# AUDIO.net
KiCad netlist of a schematic drawn in Altium Designer
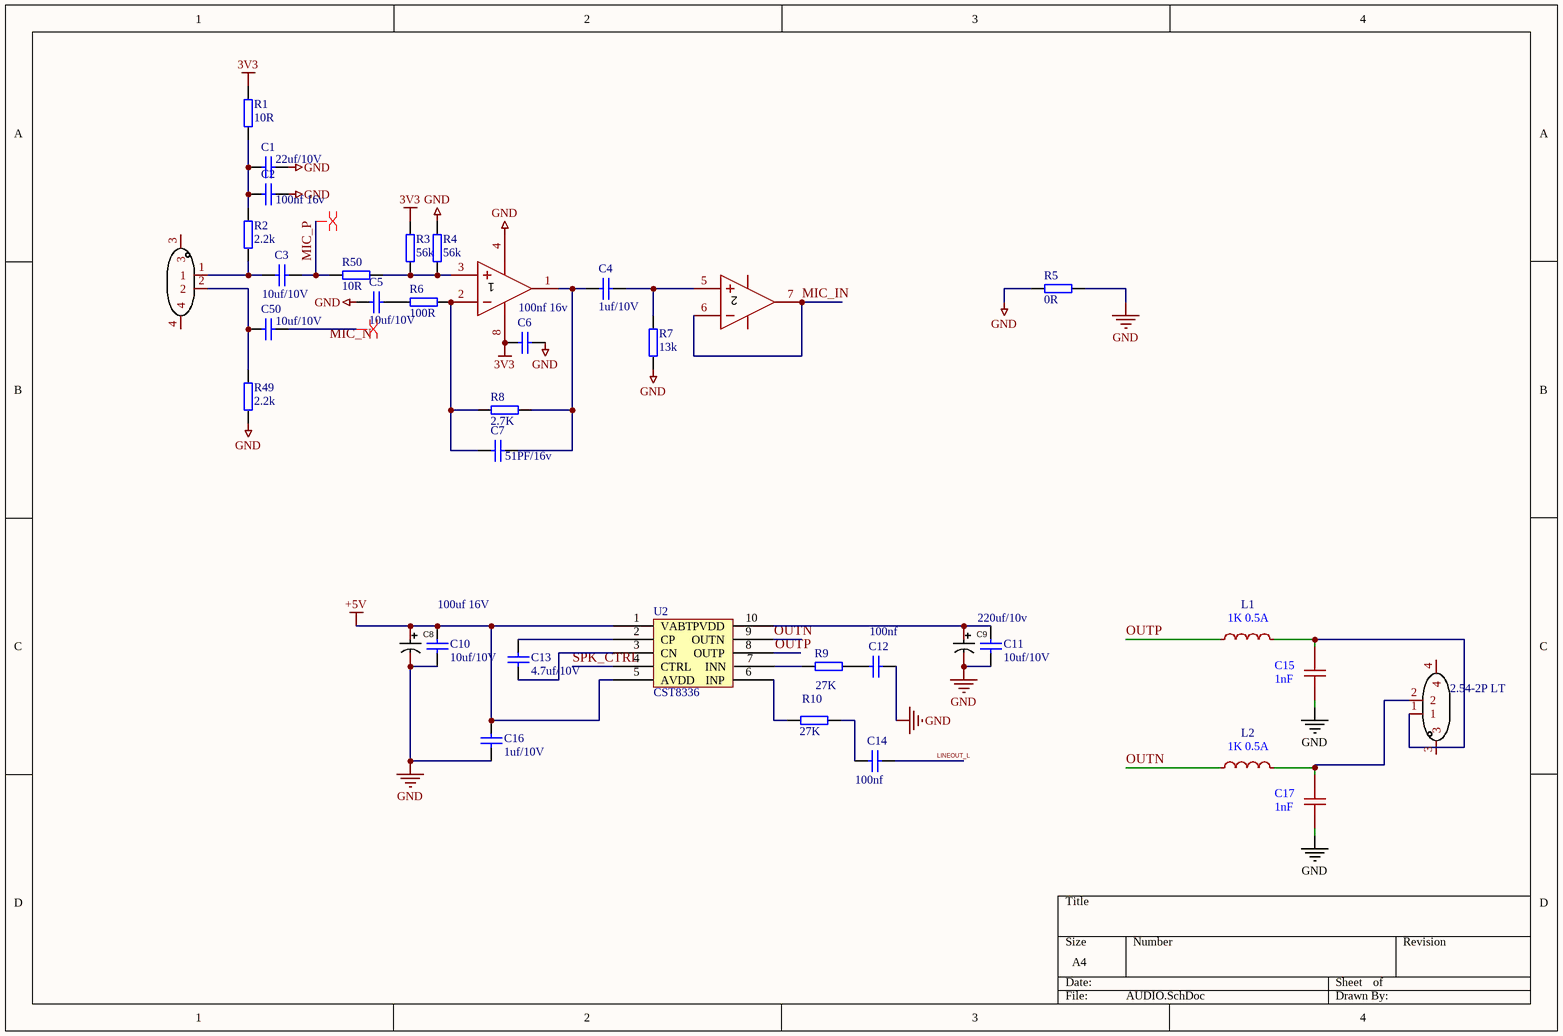
[diagram p0: AUDIO.SchDoc]

(export (version "E")
  (design (tool "Eeschema 10.0.6"))
  (components
    (comp (ref "C1")
      (value "22uf/10V")
      (footprint "0603_C")
      (description "Capacitor")
      (fields (field (name "PUBLISHER") "Altium Limited"))
      (libsource (lib "*") (part "Cap"))
    )
    (comp (ref "C2")
      (value "100nf 16v")
      (footprint "0603_C")
      (description "Capacitor")
      (fields (field (name "PUBLISHER") "Altium Limited"))
      (libsource (lib "*") (part "Cap"))
    )
    (comp (ref "C3")
      (value "10uf/10V")
      (footprint "0603_C")
      (description "Capacitor")
      (fields (field (name "PUBLISHER") "Altium Limited"))
      (libsource (lib "*") (part "Cap"))
    )
    (comp (ref "C4")
      (value "1uf/10V")
      (footprint "0603_C")
      (description "Capacitor")
      (fields (field (name "PUBLISHER") "Altium Limited"))
      (libsource (lib "*") (part "Cap"))
    )
    (comp (ref "C5")
      (value "10uf/10V")
      (footprint "0603_C")
      (description "Capacitor")
      (fields (field (name "PUBLISHER") "Altium Limited"))
      (libsource (lib "*") (part "Cap"))
    )
    (comp (ref "C6")
      (value "100nf 16v")
      (footprint "0603_C")
      (description "Capacitor")
      (fields (field (name "PUBLISHER") "Altium Limited"))
      (libsource (lib "*") (part "Cap"))
    )
    (comp (ref "C7")
      (value "51PF/16v")
      (footprint "0603_C")
      (description "Capacitor")
      (fields (field (name "PUBLISHER") "Altium Limited"))
      (libsource (lib "*") (part "Cap"))
    )
    (comp (ref "C8")
      (value "100uf 16V")
      (footprint "CAP-SMD_5*5.4")
      (fields (field (name "MANUFACTURER PART") "RVT1A221M0605"))
      (libsource (lib "altium-import") (part "root_0_RVT1A221M0605_C72494_"))
    )
    (comp (ref "C9")
      (value "220uf/10v")
      (footprint "SMD 6.3*7.7")
      (fields (field (name "MANUFACTURER PART") "RVT1A221M0605"))
      (libsource (lib "altium-import") (part "root_0_RVT1A221M0605_C72494_"))
    )
    (comp (ref "C10")
      (value "10uf/10V")
      (footprint "0603_C")
      (description "Capacitor")
      (fields (field (name "PUBLISHER") "Altium Limited"))
      (libsource (lib "*") (part "Cap"))
    )
    (comp (ref "C11")
      (value "10uf/10V")
      (footprint "0603_C")
      (description "Capacitor")
      (fields (field (name "PUBLISHER") "Altium Limited"))
      (libsource (lib "*") (part "Cap"))
    )
    (comp (ref "C12")
      (value "100nf")
      (footprint "0603_C")
      (description "Capacitor")
      (fields (field (name "PUBLISHER") "Altium Limited"))
      (libsource (lib "*") (part "Cap"))
    )
    (comp (ref "C13")
      (value "4.7uf/10V")
      (footprint "0603_C")
      (description "Capacitor")
      (fields (field (name "PUBLISHER") "Altium Limited"))
      (libsource (lib "*") (part "Cap"))
    )
    (comp (ref "C14")
      (value "100nf")
      (footprint "0603_C")
      (description "Capacitor")
      (fields (field (name "PUBLISHER") "Altium Limited"))
      (libsource (lib "*") (part "Cap"))
    )
    (comp (ref "C15")
      (value "1nF")
      (footprint "0603_c")
      (libsource (lib "altium-import") (part "root_1_CAP_0805_"))
    )
    (comp (ref "C16")
      (value "1uf/10V")
      (footprint "0603_C")
      (description "Capacitor")
      (fields (field (name "PUBLISHER") "Altium Limited"))
      (libsource (lib "*") (part "Cap"))
    )
    (comp (ref "C17")
      (value "1nF")
      (footprint "0603_c")
      (libsource (lib "altium-import") (part "root_1_CAP_0805_"))
    )
    (comp (ref "C50")
      (value "10uf/10V")
      (footprint "0603_C")
      (description "Capacitor")
      (fields (field (name "PUBLISHER") "Altium Limited"))
      (libsource (lib "*") (part "Cap"))
    )
    (comp (ref "CON1")
      (value "2.54-2P LT")
      (footprint "CONN-SMD_2.54-2PLT")
      (fields (field (name "MANUFACTURER PART") "HC-1.25-2PLT"))
      (libsource (lib "altium-import") (part "root_2_mirrored_HC-1.25-2PLT_"))
    )
    (comp (ref "L1")
      (value "1K 0.5A")
      (footprint "0805_R")
      (fields (field (name "MANUFACTURER PART") "SBK201209T-102Y-N"))
      (libsource (lib "altium-import") (part "root_0_SBK201209T-102Y-N_"))
    )
    (comp (ref "L2")
      (value "1K 0.5A")
      (footprint "0805_R")
      (libsource (lib "altium-import") (part "root_0_SBK201209T-102Y-N_"))
    )
    (comp (ref "MK1")
      (value "~")
      (footprint "CONN-SMD_1.25-2PWT")
      (fields (field (name "MANUFACTURER PART") "HC-1.25-2PLT"))
      (libsource (lib "altium-import") (part "root_0_mirrored_HC-1.25-2PLT_"))
    )
    (comp (ref "R1") (value "10R") (footprint "0603_R") (libsource (lib "DIY") (part "RES")))
    (comp (ref "R2") (value "2.2k") (footprint "0603_R") (libsource (lib "DIY") (part "RES")))
    (comp (ref "R3") (value "56k") (footprint "0603_R") (libsource (lib "DIY") (part "RES")))
    (comp (ref "R4") (value "56k") (footprint "0603_R") (libsource (lib "DIY") (part "RES")))
    (comp (ref "R5") (value "0R") (footprint "0603_R") (libsource (lib "DIY") (part "RES")))
    (comp (ref "R6") (value "100R") (footprint "0603_R") (libsource (lib "DIY") (part "RES")))
    (comp (ref "R7") (value "13k") (footprint "0603_R") (libsource (lib "DIY") (part "RES")))
    (comp (ref "R8") (value "2.7K") (footprint "0603_R") (libsource (lib "DIY") (part "RES")))
    (comp (ref "R9") (value "27K") (footprint "0603_R") (libsource (lib "DIY") (part "RES")))
    (comp (ref "R10") (value "27K") (footprint "0603_R") (libsource (lib "DIY") (part "RES")))
    (comp (ref "R49") (value "2.2k") (footprint "0603_R") (libsource (lib "DIY") (part "RES")))
    (comp (ref "R50") (value "10R") (footprint "0603_R") (libsource (lib "DIY") (part "RES")))
    (comp (ref "U1")
      (value "lmv358b-sr")
      (footprint "SOP8")
      (fields (field (name "MANUFACTURERPART") "LMV358B-SR"))
      (libsource (lib "altium-import") (part "root_2_mirrored_lmv358b-sr_"))
    )
    (comp (ref "U2") (value "CST8336") (footprint "ESOP-10") (libsource (lib "MyLib") (part "CST8336")))
  )
  (nets
    (net (code "1") (name "+5V") (class "Default")
      (node (ref "C10") (pin "1") (pinfunction "1_1") (pintype "passive"))
      (node (ref "C16") (pin "1") (pinfunction "1_1") (pintype "passive"))
      (node (ref "C8") (pin "1") (pinfunction "1_1") (pintype "passive"))
      (node (ref "U2") (pin "1") (pinfunction "VABT_1") (pintype "passive"))
      (node (ref "U2") (pin "5") (pinfunction "AVDD_5") (pintype "passive"))
    )
    (net (code "2") (name "/LINEOUT_L") (class "Default")
      (node (ref "C14") (pin "2") (pinfunction "2_2") (pintype "passive"))
    )
    (net (code "3") (name "/MIC_IN") (class "Default")
      (node (ref "U1") (pin "6") (pinfunction "INB-_6") (pintype "passive"))
      (node (ref "U1") (pin "7") (pinfunction "OUTB_7") (pintype "passive"))
    )
    (net (code "5") (name "/MIC_P") (class "Default")
      (node (ref "C3") (pin "2") (pinfunction "2_2") (pintype "passive"))
      (node (ref "R50") (pin "2") (pinfunction "2_2") (pintype "passive"))
    )
    (net (code "6") (name "/OUTN") (class "Default")
      (node (ref "L2") (pin "1") (pinfunction "1_1") (pintype "passive"))
      (node (ref "U2") (pin "9") (pinfunction "OUTN_9") (pintype "passive"))
    )
    (net (code "7") (name "/OUTP") (class "Default")
      (node (ref "L1") (pin "1") (pinfunction "1_1") (pintype "passive"))
      (node (ref "U2") (pin "8") (pinfunction "OUTP_8") (pintype "passive"))
    )
    (net (code "8") (name "/SPK_CTRL") (class "Default")
      (node (ref "U2") (pin "4") (pinfunction "CTRL_4") (pintype "passive"))
    )
    (net (code "9") (name "3V3") (class "Default")
      (node (ref "C6") (pin "2") (pinfunction "2_2") (pintype "passive"))
      (node (ref "R1") (pin "2") (pinfunction "2_2") (pintype "passive"))
      (node (ref "R3") (pin "2") (pinfunction "2_2") (pintype "passive"))
      (node (ref "U1") (pin "8") (pinfunction "+VS_8") (pintype "passive"))
    )
    (net (code "10") (name "GND") (class "Default")
      (node (ref "C1") (pin "2") (pinfunction "2_2") (pintype "passive"))
      (node (ref "C10") (pin "2") (pinfunction "2_2") (pintype "passive"))
      (node (ref "C11") (pin "2") (pinfunction "2_2") (pintype "passive"))
      (node (ref "C12") (pin "2") (pinfunction "2_2") (pintype "passive"))
      (node (ref "C15") (pin "1") (pinfunction "1_1") (pintype "passive"))
      (node (ref "C16") (pin "2") (pinfunction "2_2") (pintype "passive"))
      (node (ref "C17") (pin "1") (pinfunction "1_1") (pintype "passive"))
      (node (ref "C2") (pin "2") (pinfunction "2_2") (pintype "passive"))
      (node (ref "C5") (pin "2") (pinfunction "2_2") (pintype "passive"))
      (node (ref "C6") (pin "1") (pinfunction "1_1") (pintype "passive"))
      (node (ref "C8") (pin "2") (pinfunction "2_2") (pintype "passive"))
      (node (ref "C9") (pin "2") (pinfunction "2_2") (pintype "passive"))
      (node (ref "R4") (pin "2") (pinfunction "2_2") (pintype "passive"))
      (node (ref "R49") (pin "1") (pinfunction "1_1") (pintype "passive"))
      (node (ref "R5") (pin "1") (pinfunction "1_1") (pintype "passive"))
      (node (ref "R5") (pin "2") (pinfunction "2_2") (pintype "passive"))
      (node (ref "R7") (pin "2") (pinfunction "2_2") (pintype "passive"))
      (node (ref "U1") (pin "4") (pinfunction "-VS_4") (pintype "passive"))
    )
    (net (code "11") (name "Net-(C1-Pad1)") (class "Default")
      (node (ref "C1") (pin "1") (pinfunction "1_1") (pintype "passive"))
      (node (ref "C2") (pin "1") (pinfunction "1_1") (pintype "passive"))
      (node (ref "R1") (pin "1") (pinfunction "1_1") (pintype "passive"))
      (node (ref "R2") (pin "2") (pinfunction "2_2") (pintype "passive"))
    )
    (net (code "12") (name "Net-(C3-Pad1)") (class "Default")
      (node (ref "C3") (pin "1") (pinfunction "1_1") (pintype "passive"))
      (node (ref "MK1") (pin "1") (pinfunction "1_1") (pintype "passive"))
      (node (ref "R2") (pin "1") (pinfunction "1_1") (pintype "passive"))
    )
    (net (code "13") (name "Net-(C5-Pad1)") (class "Default")
      (node (ref "C5") (pin "1") (pinfunction "1_1") (pintype "passive"))
      (node (ref "R6") (pin "2") (pinfunction "2_2") (pintype "passive"))
    )
    (net (code "14") (name "Net-(C12-Pad1)") (class "Default")
      (node (ref "C12") (pin "1") (pinfunction "1_1") (pintype "passive"))
      (node (ref "R9") (pin "1") (pinfunction "1_1") (pintype "passive"))
    )
    (net (code "15") (name "Net-(C14-Pad1)") (class "Default")
      (node (ref "C14") (pin "1") (pinfunction "1_1") (pintype "passive"))
      (node (ref "R10") (pin "2") (pinfunction "2_2") (pintype "passive"))
    )
    (net (code "16") (name "Net-(C15-Pad2)") (class "Default")
      (node (ref "C15") (pin "2") (pinfunction "2_2") (pintype "passive"))
      (node (ref "CON1") (pin "1") (pinfunction "1_1") (pintype "passive"))
      (node (ref "L1") (pin "2") (pinfunction "2_2") (pintype "passive"))
    )
    (net (code "17") (name "Net-(C17-Pad2)") (class "Default")
      (node (ref "C17") (pin "2") (pinfunction "2_2") (pintype "passive"))
      (node (ref "CON1") (pin "2") (pinfunction "2_2") (pintype "passive"))
      (node (ref "L2") (pin "2") (pinfunction "2_2") (pintype "passive"))
    )
    (net (code "18") (name "Net-(C50-Pad1)") (class "Default")
      (node (ref "C50") (pin "1") (pinfunction "1_1") (pintype "passive"))
      (node (ref "MK1") (pin "2") (pinfunction "2_2") (pintype "passive"))
      (node (ref "R49") (pin "2") (pinfunction "2_2") (pintype "passive"))
    )
    (net (code "19") (name "Net-(U1A-INA+)") (class "Default")
      (node (ref "R3") (pin "1") (pinfunction "1_1") (pintype "passive"))
      (node (ref "R4") (pin "1") (pinfunction "1_1") (pintype "passive"))
      (node (ref "R50") (pin "1") (pinfunction "1_1") (pintype "passive"))
      (node (ref "U1") (pin "3") (pinfunction "INA+_3") (pintype "passive"))
    )
    (net (code "20") (name "Net-(U1A-INA-)") (class "Default")
      (node (ref "C7") (pin "1") (pinfunction "1_1") (pintype "passive"))
      (node (ref "R6") (pin "1") (pinfunction "1_1") (pintype "passive"))
      (node (ref "R8") (pin "2") (pinfunction "2_2") (pintype "passive"))
      (node (ref "U1") (pin "2") (pinfunction "INA-_2") (pintype "passive"))
    )
    (net (code "21") (name "Net-(U1A-OUTA)") (class "Default")
      (node (ref "C4") (pin "2") (pinfunction "2_2") (pintype "passive"))
      (node (ref "C7") (pin "2") (pinfunction "2_2") (pintype "passive"))
      (node (ref "R8") (pin "1") (pinfunction "1_1") (pintype "passive"))
      (node (ref "U1") (pin "1") (pinfunction "OUTA_1") (pintype "passive"))
    )
    (net (code "22") (name "Net-(U1B-INB+)") (class "Default")
      (node (ref "C4") (pin "1") (pinfunction "1_1") (pintype "passive"))
      (node (ref "R7") (pin "1") (pinfunction "1_1") (pintype "passive"))
      (node (ref "U1") (pin "5") (pinfunction "INB+_5") (pintype "passive"))
    )
    (net (code "23") (name "Net-(U2-CN)") (class "Default")
      (node (ref "C13") (pin "1") (pinfunction "1_1") (pintype "passive"))
      (node (ref "U2") (pin "3") (pinfunction "CN_3") (pintype "passive"))
    )
    (net (code "24") (name "Net-(U2-CP)") (class "Default")
      (node (ref "C13") (pin "2") (pinfunction "2_2") (pintype "passive"))
      (node (ref "U2") (pin "2") (pinfunction "CP_2") (pintype "passive"))
    )
    (net (code "25") (name "Net-(U2-INN)") (class "Default")
      (node (ref "R9") (pin "2") (pinfunction "2_2") (pintype "passive"))
      (node (ref "U2") (pin "7") (pinfunction "INN_7") (pintype "passive"))
    )
    (net (code "26") (name "Net-(U2-INP)") (class "Default")
      (node (ref "R10") (pin "1") (pinfunction "1_1") (pintype "passive"))
      (node (ref "U2") (pin "6") (pinfunction "INP_6") (pintype "passive"))
    )
    (net (code "27") (name "Net-(U2-PVDD)") (class "Default")
      (node (ref "C11") (pin "1") (pinfunction "1_1") (pintype "passive"))
      (node (ref "C9") (pin "1") (pinfunction "1_1") (pintype "passive"))
      (node (ref "U2") (pin "10") (pinfunction "PVDD_10") (pintype "passive"))
    )
    (net (code "28") (name "unconnected-(C50-Pad2)") (class "Default")
      (node (ref "C50") (pin "2") (pinfunction "2_2") (pintype "passive"))
    )
    (net (code "29") (name "unconnected-(CON1-Pad3)") (class "Default")
      (node (ref "CON1") (pin "3") (pinfunction "3_3") (pintype "passive"))
    )
    (net (code "30") (name "unconnected-(CON1-Pad4)") (class "Default")
      (node (ref "CON1") (pin "4") (pinfunction "4_4") (pintype "passive"))
    )
    (net (code "31") (name "unconnected-(MK1-Pad3)") (class "Default")
      (node (ref "MK1") (pin "3") (pinfunction "3_3") (pintype "passive"))
    )
    (net (code "32") (name "unconnected-(MK1-Pad4)") (class "Default")
      (node (ref "MK1") (pin "4") (pinfunction "4_4") (pintype "passive"))
    )
  )
)
